# HMVCO1.net
KiCad netlist of a schematic drawn in EAGLE
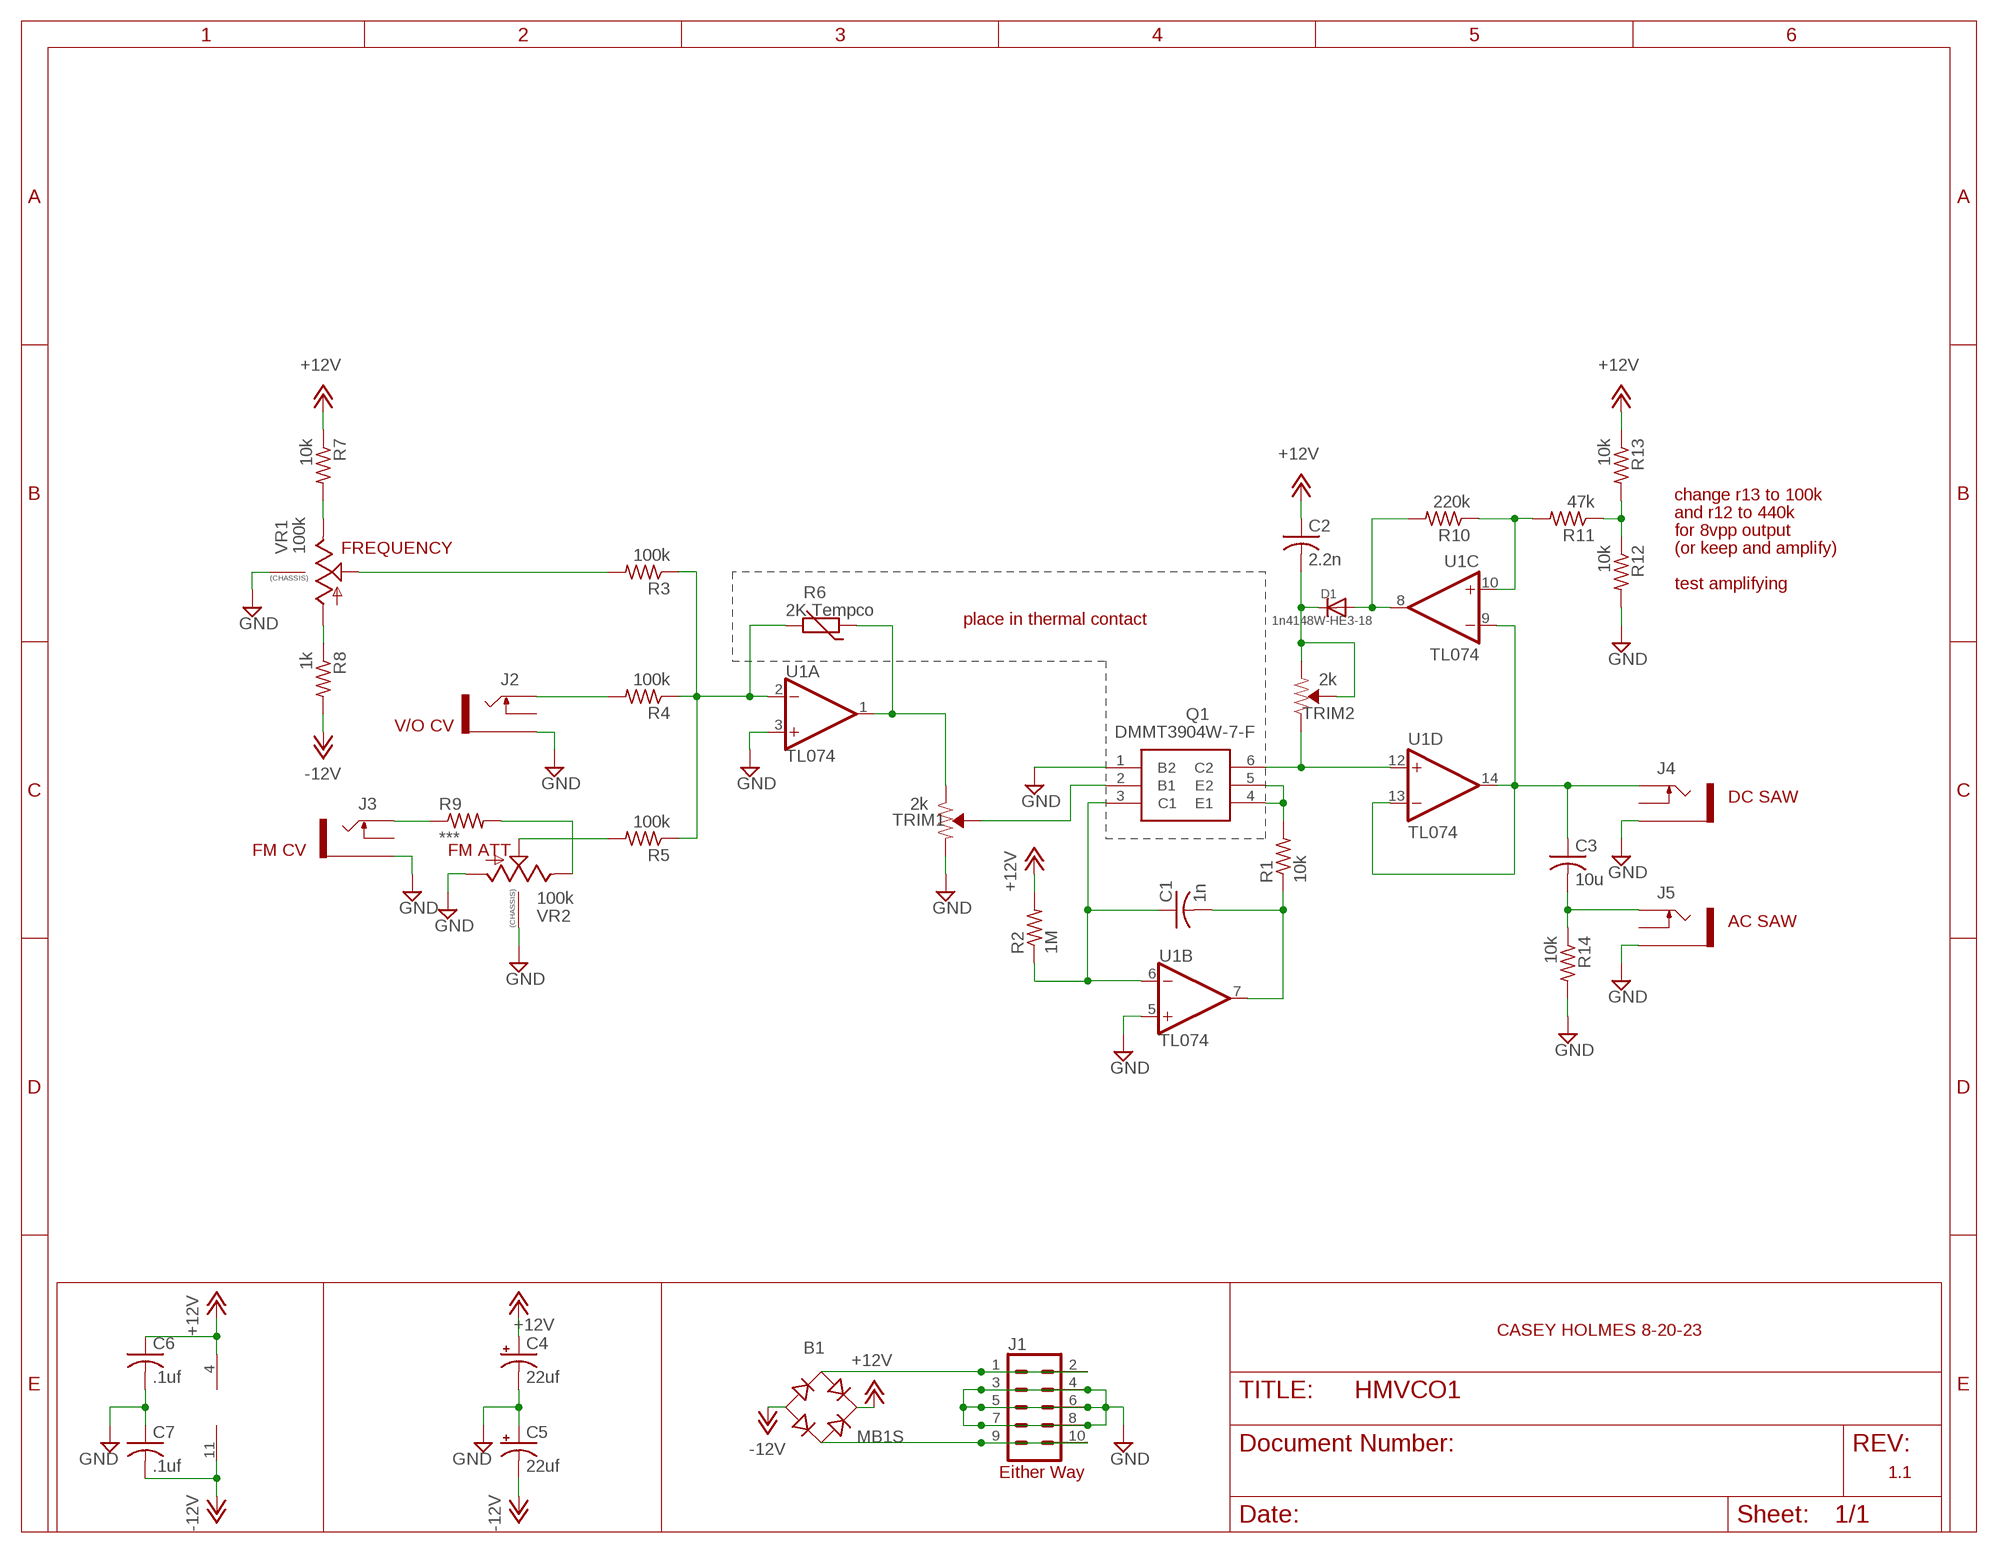
[diagram p0: schematic, sheet 1]

(export (version "E")
  (design (tool "Eeschema 10.0.6"))
  (components
    (comp (ref "B1")
      (value "MB1S")
      (footprint "eagle-import:SOIC-4")
      (libsource (lib "eagle-import") (part "MBS1"))
    )
    (comp (ref "C1")
      (value "1n")
      (footprint "eagle-import:C0603K")
      (libsource (lib "eagle-import") (part "C-USC0603K"))
    )
    (comp (ref "C2")
      (value "2.2n")
      (footprint "eagle-import:C0603K")
      (libsource (lib "eagle-import") (part "C-USC0603K"))
    )
    (comp (ref "C3")
      (value "10u")
      (footprint "eagle-import:C0603K")
      (libsource (lib "eagle-import") (part "C-USC0603K"))
    )
    (comp (ref "C4")
      (value "22uf")
      (footprint "eagle-import:PANASONIC_C")
      (libsource (lib "eagle-import") (part "CPOL-USC"))
    )
    (comp (ref "C5")
      (value "22uf")
      (footprint "eagle-import:PANASONIC_C")
      (libsource (lib "eagle-import") (part "CPOL-USC"))
    )
    (comp (ref "C6")
      (value ".1uf")
      (footprint "eagle-import:C0603K")
      (libsource (lib "eagle-import") (part "C-USC0603K"))
    )
    (comp (ref "C7")
      (value ".1uf")
      (footprint "eagle-import:C0603K")
      (libsource (lib "eagle-import") (part "C-USC0603K"))
    )
    (comp (ref "D1")
      (value "1n4148W-HE3-18")
      (footprint "eagle-import:SOD-123")
      (libsource (lib "eagle-import") (part "DIODESOD-123"))
    )
    (comp (ref "J1")
      (value "CONN_05X2PTH")
      (footprint "eagle-import:2X5")
      (libsource (lib "eagle-import") (part "CONN_05X2PTH"))
    )
    (comp (ref "J2")
      (value "THONKICONNNEW")
      (footprint "eagle-import:WQP-PJ301M-12_JACK")
      (libsource (lib "eagle-import") (part "THONKICONNNEW"))
    )
    (comp (ref "J3")
      (value "THONKICONNNEW")
      (footprint "eagle-import:WQP-PJ301M-12_JACK")
      (libsource (lib "eagle-import") (part "THONKICONNNEW"))
    )
    (comp (ref "J4")
      (value "THONKICONNNEW")
      (footprint "eagle-import:WQP-PJ301M-12_JACK")
      (libsource (lib "eagle-import") (part "THONKICONNNEW"))
    )
    (comp (ref "J5")
      (value "THONKICONNNEW")
      (footprint "eagle-import:WQP-PJ301M-12_JACK")
      (libsource (lib "eagle-import") (part "THONKICONNNEW"))
    )
    (comp (ref "Q1")
      (value "DMMT3904W-7-F")
      (footprint "eagle-import:SOT65P210X100-6N")
      (fields (field (name "MOUSER_PART_NUMBER") "621-DMMT3904W-F"))
      (libsource (lib "eagle-import") (part "DMMT3904W-7-F"))
    )
    (comp (ref "R1")
      (value "10k")
      (footprint "eagle-import:R0603")
      (libsource (lib "eagle-import") (part "R-US_R0603"))
    )
    (comp (ref "R2")
      (value "1M")
      (footprint "eagle-import:R0603")
      (libsource (lib "eagle-import") (part "R-US_R0603"))
    )
    (comp (ref "R3")
      (value "100k")
      (footprint "eagle-import:R0603")
      (libsource (lib "eagle-import") (part "R-US_R0603"))
    )
    (comp (ref "R4")
      (value "100k")
      (footprint "eagle-import:R0603")
      (libsource (lib "eagle-import") (part "R-US_R0603"))
    )
    (comp (ref "R5")
      (value "100k")
      (footprint "eagle-import:R0603")
      (libsource (lib "eagle-import") (part "R-US_R0603"))
    )
    (comp (ref "R6")
      (value "2K Tempco")
      (footprint "eagle-import:R-5")
      (libsource (lib "eagle-import") (part "THERMISTOR-5"))
    )
    (comp (ref "R7")
      (value "10k")
      (footprint "eagle-import:R0603")
      (libsource (lib "eagle-import") (part "R-US_R0603"))
    )
    (comp (ref "R8")
      (value "1k")
      (footprint "eagle-import:R0603")
      (libsource (lib "eagle-import") (part "R-US_R0603"))
    )
    (comp (ref "R9")
      (value "***")
      (footprint "eagle-import:R0603")
      (libsource (lib "eagle-import") (part "R-US_R0603"))
    )
    (comp (ref "R10")
      (value "220k")
      (footprint "eagle-import:R0603")
      (libsource (lib "eagle-import") (part "R-US_R0603"))
    )
    (comp (ref "R11")
      (value "47k")
      (footprint "eagle-import:R0603")
      (libsource (lib "eagle-import") (part "R-US_R0603"))
    )
    (comp (ref "R12")
      (value "10k")
      (footprint "eagle-import:R0603")
      (libsource (lib "eagle-import") (part "R-US_R0603"))
    )
    (comp (ref "R13")
      (value "10k")
      (footprint "eagle-import:R0603")
      (libsource (lib "eagle-import") (part "R-US_R0603"))
    )
    (comp (ref "R14")
      (value "10k")
      (footprint "eagle-import:R0603")
      (libsource (lib "eagle-import") (part "R-US_R0603"))
    )
    (comp (ref "TRIM1")
      (value "2k")
      (footprint "eagle-import:TRIMPOT-SMD-TC33X")
      (libsource (lib "eagle-import") (part "TRIMPOT-SMD-3MM-OPEN-1/10W-25%"))
    )
    (comp (ref "TRIM2")
      (value "2k")
      (footprint "eagle-import:TRIMPOT-SMD-TC33X")
      (libsource (lib "eagle-import") (part "TRIMPOT-SMD-3MM-OPEN-1/10W-25%"))
    )
    (comp (ref "U1")
      (value "TL074")
      (footprint "eagle-import:TSSOP14")
      (libsource (lib "eagle-import") (part "TL074"))
    )
    (comp (ref "VR1")
      (value "100k")
      (footprint "eagle-import:9MM_SNAP-IN_POT")
      (libsource (lib "eagle-import") (part "9MM_SNAP-IN_POT_CHASSIS"))
    )
    (comp (ref "VR2")
      (value "100k")
      (footprint "eagle-import:9MM_SNAP-IN_POT")
      (libsource (lib "eagle-import") (part "9MM_SNAP-IN_POT_CHASSIS"))
    )
  )
  (nets
    (net (code "1") (name "+12V") (class "Default")
      (node (ref "B1") (pin "+") (pinfunction "+_+") (pintype "passive"))
      (node (ref "C2") (pin "1") (pinfunction "1_1") (pintype "passive"))
      (node (ref "C4") (pin "+") (pinfunction "+_+") (pintype "passive"))
      (node (ref "C6") (pin "1") (pinfunction "1_1") (pintype "passive"))
      (node (ref "R13") (pin "1") (pinfunction "1_1") (pintype "passive"))
      (node (ref "R2") (pin "2") (pinfunction "2_2") (pintype "passive"))
      (node (ref "R7") (pin "1") (pinfunction "1_1") (pintype "passive"))
      (node (ref "U1") (pin "4") (pinfunction "V+_4") (pintype "power_in"))
    )
    (net (code "2") (name "-12V") (class "Default")
      (node (ref "B1") (pin "-") (pinfunction "-_-") (pintype "passive"))
      (node (ref "C5") (pin "-") (pinfunction "-_-") (pintype "passive"))
      (node (ref "C7") (pin "2") (pinfunction "2_2") (pintype "passive"))
      (node (ref "R8") (pin "2") (pinfunction "2_2") (pintype "passive"))
      (node (ref "U1") (pin "11") (pinfunction "V-_11") (pintype "power_in"))
    )
    (net (code "3") (name "GND") (class "Default")
      (node (ref "C4") (pin "-") (pinfunction "-_-") (pintype "passive"))
      (node (ref "C5") (pin "+") (pinfunction "+_+") (pintype "passive"))
      (node (ref "C6") (pin "2") (pinfunction "2_2") (pintype "passive"))
      (node (ref "C7") (pin "1") (pinfunction "1_1") (pintype "passive"))
      (node (ref "J1") (pin "3") (pinfunction "3_3") (pintype "passive"))
      (node (ref "J1") (pin "4") (pinfunction "4_4") (pintype "passive"))
      (node (ref "J1") (pin "5") (pinfunction "5_5") (pintype "passive"))
      (node (ref "J1") (pin "6") (pinfunction "6_6") (pintype "passive"))
      (node (ref "J1") (pin "7") (pinfunction "7_7") (pintype "passive"))
      (node (ref "J1") (pin "8") (pinfunction "8_8") (pintype "passive"))
      (node (ref "J2") (pin "P$3_SLEEVE") (pinfunction "SLEEVE_P$3_SLEEVE") (pintype "passive"))
      (node (ref "J3") (pin "P$3_SLEEVE") (pinfunction "SLEEVE_P$3_SLEEVE") (pintype "passive"))
      (node (ref "J4") (pin "P$3_SLEEVE") (pinfunction "SLEEVE_P$3_SLEEVE") (pintype "passive"))
      (node (ref "J5") (pin "P$3_SLEEVE") (pinfunction "SLEEVE_P$3_SLEEVE") (pintype "passive"))
      (node (ref "Q1") (pin "1") (pinfunction "B2_1") (pintype "bidirectional"))
      (node (ref "R12") (pin "2") (pinfunction "2_2") (pintype "passive"))
      (node (ref "R14") (pin "2") (pinfunction "2_2") (pintype "passive"))
      (node (ref "TRIM1") (pin "3") (pinfunction "CCW_3") (pintype "passive"))
      (node (ref "U1") (pin "3") (pinfunction "+IN_3") (pintype "input"))
      (node (ref "U1") (pin "5") (pinfunction "+IN_5") (pintype "input"))
      (node (ref "VR1") (pin "CHASSIS1") (pinfunction "P$1_CHASSIS1") (pintype "passive"))
      (node (ref "VR1") (pin "CHASSIS2") (pinfunction "P$1_CHASSIS2") (pintype "passive"))
      (node (ref "VR2") (pin "1") (pinfunction "A_1") (pintype "passive"))
      (node (ref "VR2") (pin "CHASSIS1") (pinfunction "P$1_CHASSIS1") (pintype "passive"))
      (node (ref "VR2") (pin "CHASSIS2") (pinfunction "P$1_CHASSIS2") (pintype "passive"))
    )
    (net (code "4") (name "Net-(B1-AC1)") (class "Default")
      (node (ref "B1") (pin "~1") (pinfunction "AC1_~1") (pintype "passive"))
      (node (ref "J1") (pin "1") (pinfunction "1_1") (pintype "passive"))
      (node (ref "J1") (pin "2") (pinfunction "2_2") (pintype "passive"))
    )
    (net (code "5") (name "Net-(B1-AC2)") (class "Default")
      (node (ref "B1") (pin "~2") (pinfunction "AC2_~2") (pintype "passive"))
      (node (ref "J1") (pin "10") (pinfunction "10_10") (pintype "passive"))
      (node (ref "J1") (pin "9") (pinfunction "9_9") (pintype "passive"))
    )
    (net (code "6") (name "Net-(J2-TIP)") (class "Default")
      (node (ref "J2") (pin "P$1_TIP") (pinfunction "TIP_P$1_TIP") (pintype "passive"))
      (node (ref "R4") (pin "2") (pinfunction "2_2") (pintype "passive"))
    )
    (net (code "7") (name "Net-(J3-TIP)") (class "Default")
      (node (ref "J3") (pin "P$1_TIP") (pinfunction "TIP_P$1_TIP") (pintype "passive"))
      (node (ref "R9") (pin "1") (pinfunction "1_1") (pintype "passive"))
    )
    (net (code "8") (name "Net-(J4-TIP)") (class "Default")
      (node (ref "C3") (pin "1") (pinfunction "1_1") (pintype "passive"))
      (node (ref "J4") (pin "P$1_TIP") (pinfunction "TIP_P$1_TIP") (pintype "passive"))
      (node (ref "U1") (pin "13") (pinfunction "-IN_13") (pintype "input"))
      (node (ref "U1") (pin "14") (pinfunction "OUT_14") (pintype "output"))
      (node (ref "U1") (pin "9") (pinfunction "-IN_9") (pintype "input"))
    )
    (net (code "9") (name "Net-(J5-TIP)") (class "Default")
      (node (ref "C3") (pin "2") (pinfunction "2_2") (pintype "passive"))
      (node (ref "J5") (pin "P$1_TIP") (pinfunction "TIP_P$1_TIP") (pintype "passive"))
      (node (ref "R14") (pin "1") (pinfunction "1_1") (pintype "passive"))
    )
    (net (code "10") (name "Net-(Q1-B1)") (class "Default")
      (node (ref "Q1") (pin "2") (pinfunction "B1_2") (pintype "bidirectional"))
      (node (ref "TRIM1") (pin "2") (pinfunction "WIPER_2") (pintype "passive"))
    )
    (net (code "11") (name "Net-(Q1-C1)") (class "Default")
      (node (ref "C1") (pin "1") (pinfunction "1_1") (pintype "passive"))
      (node (ref "Q1") (pin "3") (pinfunction "C1_3") (pintype "bidirectional"))
      (node (ref "R2") (pin "1") (pinfunction "1_1") (pintype "passive"))
      (node (ref "U1") (pin "6") (pinfunction "-IN_6") (pintype "input"))
    )
    (net (code "12") (name "Net-(Q1-C2)") (class "Default")
      (node (ref "Q1") (pin "6") (pinfunction "C2_6") (pintype "bidirectional"))
      (node (ref "TRIM2") (pin "1") (pinfunction "CW_1") (pintype "passive"))
      (node (ref "U1") (pin "12") (pinfunction "+IN_12") (pintype "input"))
    )
    (net (code "13") (name "Net-(Q1-E1)") (class "Default")
      (node (ref "Q1") (pin "4") (pinfunction "E1_4") (pintype "bidirectional"))
      (node (ref "Q1") (pin "5") (pinfunction "E2_5") (pintype "bidirectional"))
      (node (ref "R1") (pin "2") (pinfunction "2_2") (pintype "passive"))
    )
    (net (code "14") (name "Net-(R11-Pad1)") (class "Default")
      (node (ref "R11") (pin "1") (pinfunction "1_1") (pintype "passive"))
      (node (ref "R12") (pin "1") (pinfunction "1_1") (pintype "passive"))
      (node (ref "R13") (pin "2") (pinfunction "2_2") (pintype "passive"))
    )
    (net (code "15") (name "Net-(TRIM1-CW)") (class "Default")
      (node (ref "R6") (pin "1") (pinfunction "1_1") (pintype "passive"))
      (node (ref "TRIM1") (pin "1") (pinfunction "CW_1") (pintype "passive"))
      (node (ref "U1") (pin "1") (pinfunction "OUT_1") (pintype "output"))
    )
    (net (code "16") (name "Net-(TRIM2-CCW)") (class "Default")
      (node (ref "C2") (pin "2") (pinfunction "2_2") (pintype "passive"))
      (node (ref "D1") (pin "C") (pinfunction "C_C") (pintype "passive"))
      (node (ref "TRIM2") (pin "2") (pinfunction "WIPER_2") (pintype "passive"))
      (node (ref "TRIM2") (pin "3") (pinfunction "CCW_3") (pintype "passive"))
    )
    (net (code "17") (name "Net-(U1A--IN)") (class "Default")
      (node (ref "R3") (pin "1") (pinfunction "1_1") (pintype "passive"))
      (node (ref "R4") (pin "1") (pinfunction "1_1") (pintype "passive"))
      (node (ref "R5") (pin "1") (pinfunction "1_1") (pintype "passive"))
      (node (ref "R6") (pin "2") (pinfunction "2_2") (pintype "passive"))
      (node (ref "U1") (pin "2") (pinfunction "-IN_2") (pintype "input"))
    )
    (net (code "18") (name "Net-(U1B-OUT)") (class "Default")
      (node (ref "C1") (pin "2") (pinfunction "2_2") (pintype "passive"))
      (node (ref "R1") (pin "1") (pinfunction "1_1") (pintype "passive"))
      (node (ref "U1") (pin "7") (pinfunction "OUT_7") (pintype "output"))
    )
    (net (code "19") (name "Net-(U1C-+IN)") (class "Default")
      (node (ref "R10") (pin "1") (pinfunction "1_1") (pintype "passive"))
      (node (ref "R11") (pin "2") (pinfunction "2_2") (pintype "passive"))
      (node (ref "U1") (pin "10") (pinfunction "+IN_10") (pintype "input"))
    )
    (net (code "20") (name "Net-(U1C-OUT)") (class "Default")
      (node (ref "D1") (pin "A") (pinfunction "A_A") (pintype "passive"))
      (node (ref "R10") (pin "2") (pinfunction "2_2") (pintype "passive"))
      (node (ref "U1") (pin "8") (pinfunction "OUT_8") (pintype "output"))
    )
    (net (code "21") (name "Net-(VR1-A)") (class "Default")
      (node (ref "R8") (pin "1") (pinfunction "1_1") (pintype "passive"))
      (node (ref "VR1") (pin "1") (pinfunction "A_1") (pintype "passive"))
    )
    (net (code "22") (name "Net-(VR1-E)") (class "Default")
      (node (ref "R7") (pin "2") (pinfunction "2_2") (pintype "passive"))
      (node (ref "VR1") (pin "3") (pinfunction "E_3") (pintype "passive"))
    )
    (net (code "23") (name "Net-(VR1-S)") (class "Default")
      (node (ref "R3") (pin "2") (pinfunction "2_2") (pintype "passive"))
      (node (ref "VR1") (pin "2") (pinfunction "S_2") (pintype "passive"))
    )
    (net (code "24") (name "Net-(VR2-E)") (class "Default")
      (node (ref "R9") (pin "2") (pinfunction "2_2") (pintype "passive"))
      (node (ref "VR2") (pin "3") (pinfunction "E_3") (pintype "passive"))
    )
    (net (code "25") (name "Net-(VR2-S)") (class "Default")
      (node (ref "R5") (pin "2") (pinfunction "2_2") (pintype "passive"))
      (node (ref "VR2") (pin "2") (pinfunction "S_2") (pintype "passive"))
    )
    (net (code "26") (name "unconnected-(J2-SWITCH-PadP$2_SWITCH)") (class "Default")
      (node (ref "J2") (pin "P$2_SWITCH") (pinfunction "SWITCH_P$2_SWITCH") (pintype "passive"))
    )
    (net (code "27") (name "unconnected-(J3-SWITCH-PadP$2_SWITCH)") (class "Default")
      (node (ref "J3") (pin "P$2_SWITCH") (pinfunction "SWITCH_P$2_SWITCH") (pintype "passive"))
    )
    (net (code "28") (name "unconnected-(J4-SWITCH-PadP$2_SWITCH)") (class "Default")
      (node (ref "J4") (pin "P$2_SWITCH") (pinfunction "SWITCH_P$2_SWITCH") (pintype "passive"))
    )
    (net (code "29") (name "unconnected-(J5-SWITCH-PadP$2_SWITCH)") (class "Default")
      (node (ref "J5") (pin "P$2_SWITCH") (pinfunction "SWITCH_P$2_SWITCH") (pintype "passive"))
    )
  )
)
